# TTTConsole.net
KiCad netlist of a schematic drawn in Altium Designer
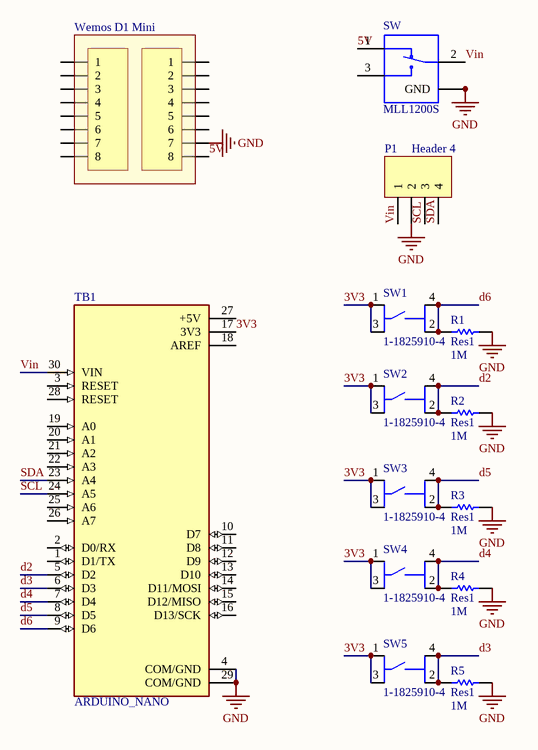
[diagram p0: TTTConsole.SchDoc]

(export (version "E")
  (design (tool "Eeschema 10.0.6"))
  (components
    (comp (ref "P1")
      (value "Header 4")
      (footprint "HDR1X4")
      (description "Header, 4-Pin")
      (fields (field (name "PUBLISHER") "Altium Limited"))
      (libsource (lib "Miscellaneous Connectors") (part "Header 4"))
    )
    (comp (ref "P2")
      (value "Header 8")
      (footprint "HDR1X8")
      (description "Header, 8-Pin")
      (fields (field (name "PUBLISHER") "Altium Limited"))
      (libsource (lib "") (part "Header 8_1"))
    )
    (comp (ref "P3")
      (value "Header 8")
      (footprint "HDR1X8")
      (description "Header, 8-Pin")
      (fields (field (name "PUBLISHER") "Altium Limited"))
      (libsource (lib "Miscellaneous Connectors") (part "Header 8"))
    )
    (comp (ref "R1")
      (value "Res1")
      (footprint "AXIAL-0.3")
      (description "Resistor")
      (fields (field (name "ALTIUM_VALUE") "1M") (field (name "PUBLISHER") "Altium Limited"))
      (libsource (lib "Miscellaneous Devices") (part "Res1"))
    )
    (comp (ref "R2")
      (value "Res1")
      (footprint "AXIAL-0.3")
      (description "Resistor")
      (fields (field (name "ALTIUM_VALUE") "1M") (field (name "PUBLISHER") "Altium Limited"))
      (libsource (lib "Miscellaneous Devices") (part "Res1"))
    )
    (comp (ref "R3")
      (value "Res1")
      (footprint "AXIAL-0.3")
      (description "Resistor")
      (fields (field (name "ALTIUM_VALUE") "1M") (field (name "PUBLISHER") "Altium Limited"))
      (libsource (lib "Miscellaneous Devices") (part "Res1"))
    )
    (comp (ref "R4")
      (value "Res1")
      (footprint "AXIAL-0.3")
      (description "Resistor")
      (fields (field (name "ALTIUM_VALUE") "1M") (field (name "PUBLISHER") "Altium Limited"))
      (libsource (lib "Miscellaneous Devices") (part "Res1"))
    )
    (comp (ref "R5")
      (value "Res1")
      (footprint "AXIAL-0.3")
      (description "Resistor")
      (fields (field (name "ALTIUM_VALUE") "1M") (field (name "PUBLISHER") "Altium Limited"))
      (libsource (lib "Miscellaneous Devices") (part "Res1"))
    )
    (comp (ref "SW")
      (value "MLL1200S")
      (footprint "SW_MLL1200S")
      (description "Slide Switch SPDT Surface Mount, Right Angle")
      (fields (field (name "MF") "TE Connectivity") (field (name "DIGI-KEY_PART_NUMBER") "450-1577-ND"))
      (libsource (lib "MLL1200S") (part "MLL1200S"))
    )
    (comp (ref "SW1")
      (value "1-1825910-4")
      (footprint "TE_1-1825910-4")
      (description "Switch Tactile OFF _ON_ SPST Round Button PC Pins 0.05A 24VDC 100000Cycles 1.56N Thru-Hole")
      (fields (field (name "MF") "TE Connectivity"))
      (libsource (lib "1-1825910-4") (part "1-1825910-4"))
    )
    (comp (ref "SW2")
      (value "1-1825910-4")
      (footprint "TE_1-1825910-4")
      (description "Switch Tactile OFF _ON_ SPST Round Button PC Pins 0.05A 24VDC 100000Cycles 1.56N Thru-Hole")
      (fields (field (name "MF") "TE Connectivity"))
      (libsource (lib "1-1825910-4") (part "1-1825910-4"))
    )
    (comp (ref "SW3")
      (value "1-1825910-4")
      (footprint "TE_1-1825910-4")
      (description "Switch Tactile OFF _ON_ SPST Round Button PC Pins 0.05A 24VDC 100000Cycles 1.56N Thru-Hole")
      (fields (field (name "MF") "TE Connectivity"))
      (libsource (lib "1-1825910-4") (part "1-1825910-4"))
    )
    (comp (ref "SW4")
      (value "1-1825910-4")
      (footprint "TE_1-1825910-4")
      (description "Switch Tactile OFF _ON_ SPST Round Button PC Pins 0.05A 24VDC 100000Cycles 1.56N Thru-Hole")
      (fields (field (name "MF") "TE Connectivity"))
      (libsource (lib "1-1825910-4") (part "1-1825910-4"))
    )
    (comp (ref "SW5")
      (value "1-1825910-4")
      (footprint "TE_1-1825910-4")
      (description "Switch Tactile OFF _ON_ SPST Round Button PC Pins 0.05A 24VDC 100000Cycles 1.56N Thru-Hole")
      (fields (field (name "MF") "TE Connectivity"))
      (libsource (lib "1-1825910-4") (part "1-1825910-4"))
    )
    (comp (ref "TB1")
      (value "ARDUINO_NANO")
      (footprint "SHIELD_ARDUINO_NANO")
      (description "ATSAMD21G18A Arduino Nano 33 IoT SAM D ARMÂ® CortexÂ®-M0+ MCU 32-Bit Embedded Evaluation Board")
      (fields (field (name "MP") "ARDUINO NANO") (field (name "MF") "Arduino"))
      (libsource (lib "ARDUINO_NANO") (part "ARDUINO_NANO"))
    )
  )
  (nets
    (net (code "1") (name "/3V3") (class "Default")
      (node (ref "SW1") (pin "1") (pinfunction "1_1") (pintype "passive"))
      (node (ref "SW1") (pin "3") (pinfunction "3_3") (pintype "passive"))
      (node (ref "SW2") (pin "1") (pinfunction "1_1") (pintype "passive"))
      (node (ref "SW2") (pin "3") (pinfunction "3_3") (pintype "passive"))
      (node (ref "SW3") (pin "1") (pinfunction "1_1") (pintype "passive"))
      (node (ref "SW3") (pin "3") (pinfunction "3_3") (pintype "passive"))
      (node (ref "SW4") (pin "1") (pinfunction "1_1") (pintype "passive"))
      (node (ref "SW4") (pin "3") (pinfunction "3_3") (pintype "passive"))
      (node (ref "SW5") (pin "1") (pinfunction "1_1") (pintype "passive"))
      (node (ref "SW5") (pin "3") (pinfunction "3_3") (pintype "passive"))
      (node (ref "TB1") (pin "17") (pinfunction "3V3_17") (pintype "power_in"))
    )
    (net (code "2") (name "/5V") (class "Default")
      (node (ref "P3") (pin "8") (pinfunction "8_8") (pintype "passive"))
      (node (ref "SW") (pin "1") (pinfunction "1_1") (pintype "passive"))
    )
    (net (code "3") (name "/SCL") (class "Default")
      (node (ref "P1") (pin "3") (pinfunction "3_3") (pintype "passive"))
      (node (ref "TB1") (pin "24") (pinfunction "A5_24") (pintype "input"))
    )
    (net (code "4") (name "/SDA") (class "Default")
      (node (ref "P1") (pin "4") (pinfunction "4_4") (pintype "passive"))
      (node (ref "TB1") (pin "23") (pinfunction "A4_23") (pintype "input"))
    )
    (net (code "5") (name "/Vin") (class "Default")
      (node (ref "P1") (pin "1") (pinfunction "1_1") (pintype "passive"))
      (node (ref "SW") (pin "2") (pinfunction "2_2") (pintype "passive"))
      (node (ref "TB1") (pin "30") (pinfunction "VIN_30") (pintype "input"))
    )
    (net (code "6") (name "/d2") (class "Default")
      (node (ref "R2") (pin "1") (pinfunction "1_1") (pintype "passive"))
      (node (ref "SW2") (pin "2") (pinfunction "2_2") (pintype "passive"))
      (node (ref "SW2") (pin "4") (pinfunction "4_4") (pintype "passive"))
      (node (ref "TB1") (pin "5") (pinfunction "D2_5") (pintype "bidirectional"))
    )
    (net (code "7") (name "/d3") (class "Default")
      (node (ref "R5") (pin "1") (pinfunction "1_1") (pintype "passive"))
      (node (ref "SW5") (pin "2") (pinfunction "2_2") (pintype "passive"))
      (node (ref "SW5") (pin "4") (pinfunction "4_4") (pintype "passive"))
      (node (ref "TB1") (pin "6") (pinfunction "D3_6") (pintype "bidirectional"))
    )
    (net (code "8") (name "/d4") (class "Default")
      (node (ref "R4") (pin "1") (pinfunction "1_1") (pintype "passive"))
      (node (ref "SW4") (pin "2") (pinfunction "2_2") (pintype "passive"))
      (node (ref "SW4") (pin "4") (pinfunction "4_4") (pintype "passive"))
      (node (ref "TB1") (pin "7") (pinfunction "D4_7") (pintype "bidirectional"))
    )
    (net (code "9") (name "/d5") (class "Default")
      (node (ref "R3") (pin "1") (pinfunction "1_1") (pintype "passive"))
      (node (ref "SW3") (pin "2") (pinfunction "2_2") (pintype "passive"))
      (node (ref "SW3") (pin "4") (pinfunction "4_4") (pintype "passive"))
      (node (ref "TB1") (pin "8") (pinfunction "D5_8") (pintype "bidirectional"))
    )
    (net (code "10") (name "/d6") (class "Default")
      (node (ref "R1") (pin "1") (pinfunction "1_1") (pintype "passive"))
      (node (ref "SW1") (pin "2") (pinfunction "2_2") (pintype "passive"))
      (node (ref "SW1") (pin "4") (pinfunction "4_4") (pintype "passive"))
      (node (ref "TB1") (pin "9") (pinfunction "D6_9") (pintype "bidirectional"))
    )
    (net (code "11") (name "GND") (class "Default")
      (node (ref "P1") (pin "2") (pinfunction "2_2") (pintype "passive"))
      (node (ref "P3") (pin "7") (pinfunction "7_7") (pintype "passive"))
      (node (ref "R1") (pin "2") (pinfunction "2_2") (pintype "passive"))
      (node (ref "R2") (pin "2") (pinfunction "2_2") (pintype "passive"))
      (node (ref "R3") (pin "2") (pinfunction "2_2") (pintype "passive"))
      (node (ref "R4") (pin "2") (pinfunction "2_2") (pintype "passive"))
      (node (ref "R5") (pin "2") (pinfunction "2_2") (pintype "passive"))
      (node (ref "SW") (pin "G1") (pinfunction "GND_G1") (pintype "power_in"))
      (node (ref "SW") (pin "G2") (pinfunction "GND_G2") (pintype "power_in"))
      (node (ref "SW") (pin "G3") (pinfunction "GND_G3") (pintype "power_in"))
      (node (ref "SW") (pin "G4") (pinfunction "GND_G4") (pintype "power_in"))
      (node (ref "TB1") (pin "29") (pinfunction "COM/GND_29") (pintype "power_in"))
      (node (ref "TB1") (pin "4") (pinfunction "COM/GND_4") (pintype "power_in"))
    )
    (net (code "12") (name "unconnected-(P2-Pad1)") (class "Default")
      (node (ref "P2") (pin "1") (pinfunction "1_1") (pintype "passive"))
    )
    (net (code "13") (name "unconnected-(P2-Pad2)") (class "Default")
      (node (ref "P2") (pin "2") (pinfunction "2_2") (pintype "passive"))
    )
    (net (code "14") (name "unconnected-(P2-Pad3)") (class "Default")
      (node (ref "P2") (pin "3") (pinfunction "3_3") (pintype "passive"))
    )
    (net (code "15") (name "unconnected-(P2-Pad4)") (class "Default")
      (node (ref "P2") (pin "4") (pinfunction "4_4") (pintype "passive"))
    )
    (net (code "16") (name "unconnected-(P2-Pad5)") (class "Default")
      (node (ref "P2") (pin "5") (pinfunction "5_5") (pintype "passive"))
    )
    (net (code "17") (name "unconnected-(P2-Pad6)") (class "Default")
      (node (ref "P2") (pin "6") (pinfunction "6_6") (pintype "passive"))
    )
    (net (code "18") (name "unconnected-(P2-Pad7)") (class "Default")
      (node (ref "P2") (pin "7") (pinfunction "7_7") (pintype "passive"))
    )
    (net (code "19") (name "unconnected-(P2-Pad8)") (class "Default")
      (node (ref "P2") (pin "8") (pinfunction "8_8") (pintype "passive"))
    )
    (net (code "20") (name "unconnected-(P3-Pad1)") (class "Default")
      (node (ref "P3") (pin "1") (pinfunction "1_1") (pintype "passive"))
    )
    (net (code "21") (name "unconnected-(P3-Pad2)") (class "Default")
      (node (ref "P3") (pin "2") (pinfunction "2_2") (pintype "passive"))
    )
    (net (code "22") (name "unconnected-(P3-Pad3)") (class "Default")
      (node (ref "P3") (pin "3") (pinfunction "3_3") (pintype "passive"))
    )
    (net (code "23") (name "unconnected-(P3-Pad4)") (class "Default")
      (node (ref "P3") (pin "4") (pinfunction "4_4") (pintype "passive"))
    )
    (net (code "24") (name "unconnected-(P3-Pad5)") (class "Default")
      (node (ref "P3") (pin "5") (pinfunction "5_5") (pintype "passive"))
    )
    (net (code "25") (name "unconnected-(P3-Pad6)") (class "Default")
      (node (ref "P3") (pin "6") (pinfunction "6_6") (pintype "passive"))
    )
    (net (code "26") (name "unconnected-(SW-Pad3)") (class "Default")
      (node (ref "SW") (pin "3") (pinfunction "3_3") (pintype "passive"))
    )
    (net (code "27") (name "unconnected-(TB1-+5V-Pad27)") (class "Default")
      (node (ref "TB1") (pin "27") (pinfunction "+5V_27") (pintype "power_in"))
    )
    (net (code "28") (name "unconnected-(TB1-A0-Pad19)") (class "Default")
      (node (ref "TB1") (pin "19") (pinfunction "A0_19") (pintype "input"))
    )
    (net (code "29") (name "unconnected-(TB1-A1-Pad20)") (class "Default")
      (node (ref "TB1") (pin "20") (pinfunction "A1_20") (pintype "input"))
    )
    (net (code "30") (name "unconnected-(TB1-A2-Pad21)") (class "Default")
      (node (ref "TB1") (pin "21") (pinfunction "A2_21") (pintype "input"))
    )
    (net (code "31") (name "unconnected-(TB1-A3-Pad22)") (class "Default")
      (node (ref "TB1") (pin "22") (pinfunction "A3_22") (pintype "input"))
    )
    (net (code "32") (name "unconnected-(TB1-A6-Pad25)") (class "Default")
      (node (ref "TB1") (pin "25") (pinfunction "A6_25") (pintype "input"))
    )
    (net (code "33") (name "unconnected-(TB1-A7-Pad26)") (class "Default")
      (node (ref "TB1") (pin "26") (pinfunction "A7_26") (pintype "input"))
    )
    (net (code "34") (name "unconnected-(TB1-AREF-Pad18)") (class "Default")
      (node (ref "TB1") (pin "18") (pinfunction "AREF_18") (pintype "power_in"))
    )
    (net (code "35") (name "unconnected-(TB1-D0{slash}RX-Pad2)") (class "Default")
      (node (ref "TB1") (pin "2") (pinfunction "D0/RX_2") (pintype "bidirectional"))
    )
    (net (code "36") (name "unconnected-(TB1-D1{slash}TX-Pad1)") (class "Default")
      (node (ref "TB1") (pin "1") (pinfunction "D1/TX_1") (pintype "bidirectional"))
    )
    (net (code "37") (name "unconnected-(TB1-D7-Pad10)") (class "Default")
      (node (ref "TB1") (pin "10") (pinfunction "D7_10") (pintype "bidirectional"))
    )
    (net (code "38") (name "unconnected-(TB1-D8-Pad11)") (class "Default")
      (node (ref "TB1") (pin "11") (pinfunction "D8_11") (pintype "bidirectional"))
    )
    (net (code "39") (name "unconnected-(TB1-D9-Pad12)") (class "Default")
      (node (ref "TB1") (pin "12") (pinfunction "D9_12") (pintype "bidirectional"))
    )
    (net (code "40") (name "unconnected-(TB1-D10-Pad13)") (class "Default")
      (node (ref "TB1") (pin "13") (pinfunction "D10_13") (pintype "bidirectional"))
    )
    (net (code "41") (name "unconnected-(TB1-D11{slash}MOSI-Pad14)") (class "Default")
      (node (ref "TB1") (pin "14") (pinfunction "D11/MOSI_14") (pintype "bidirectional"))
    )
    (net (code "42") (name "unconnected-(TB1-D12{slash}MISO-Pad15)") (class "Default")
      (node (ref "TB1") (pin "15") (pinfunction "D12/MISO_15") (pintype "bidirectional"))
    )
    (net (code "43") (name "unconnected-(TB1-D13{slash}SCK-Pad16)") (class "Default")
      (node (ref "TB1") (pin "16") (pinfunction "D13/SCK_16") (pintype "bidirectional"))
    )
    (net (code "44") (name "unconnected-(TB1-RESET-Pad3)") (class "Default")
      (node (ref "TB1") (pin "3") (pinfunction "RESET_3") (pintype "input"))
    )
    (net (code "45") (name "unconnected-(TB1-RESET-Pad28)") (class "Default")
      (node (ref "TB1") (pin "28") (pinfunction "RESET_28") (pintype "input"))
    )
  )
)
